# powermon.net
KiCad netlist of a schematic drawn in EAGLE
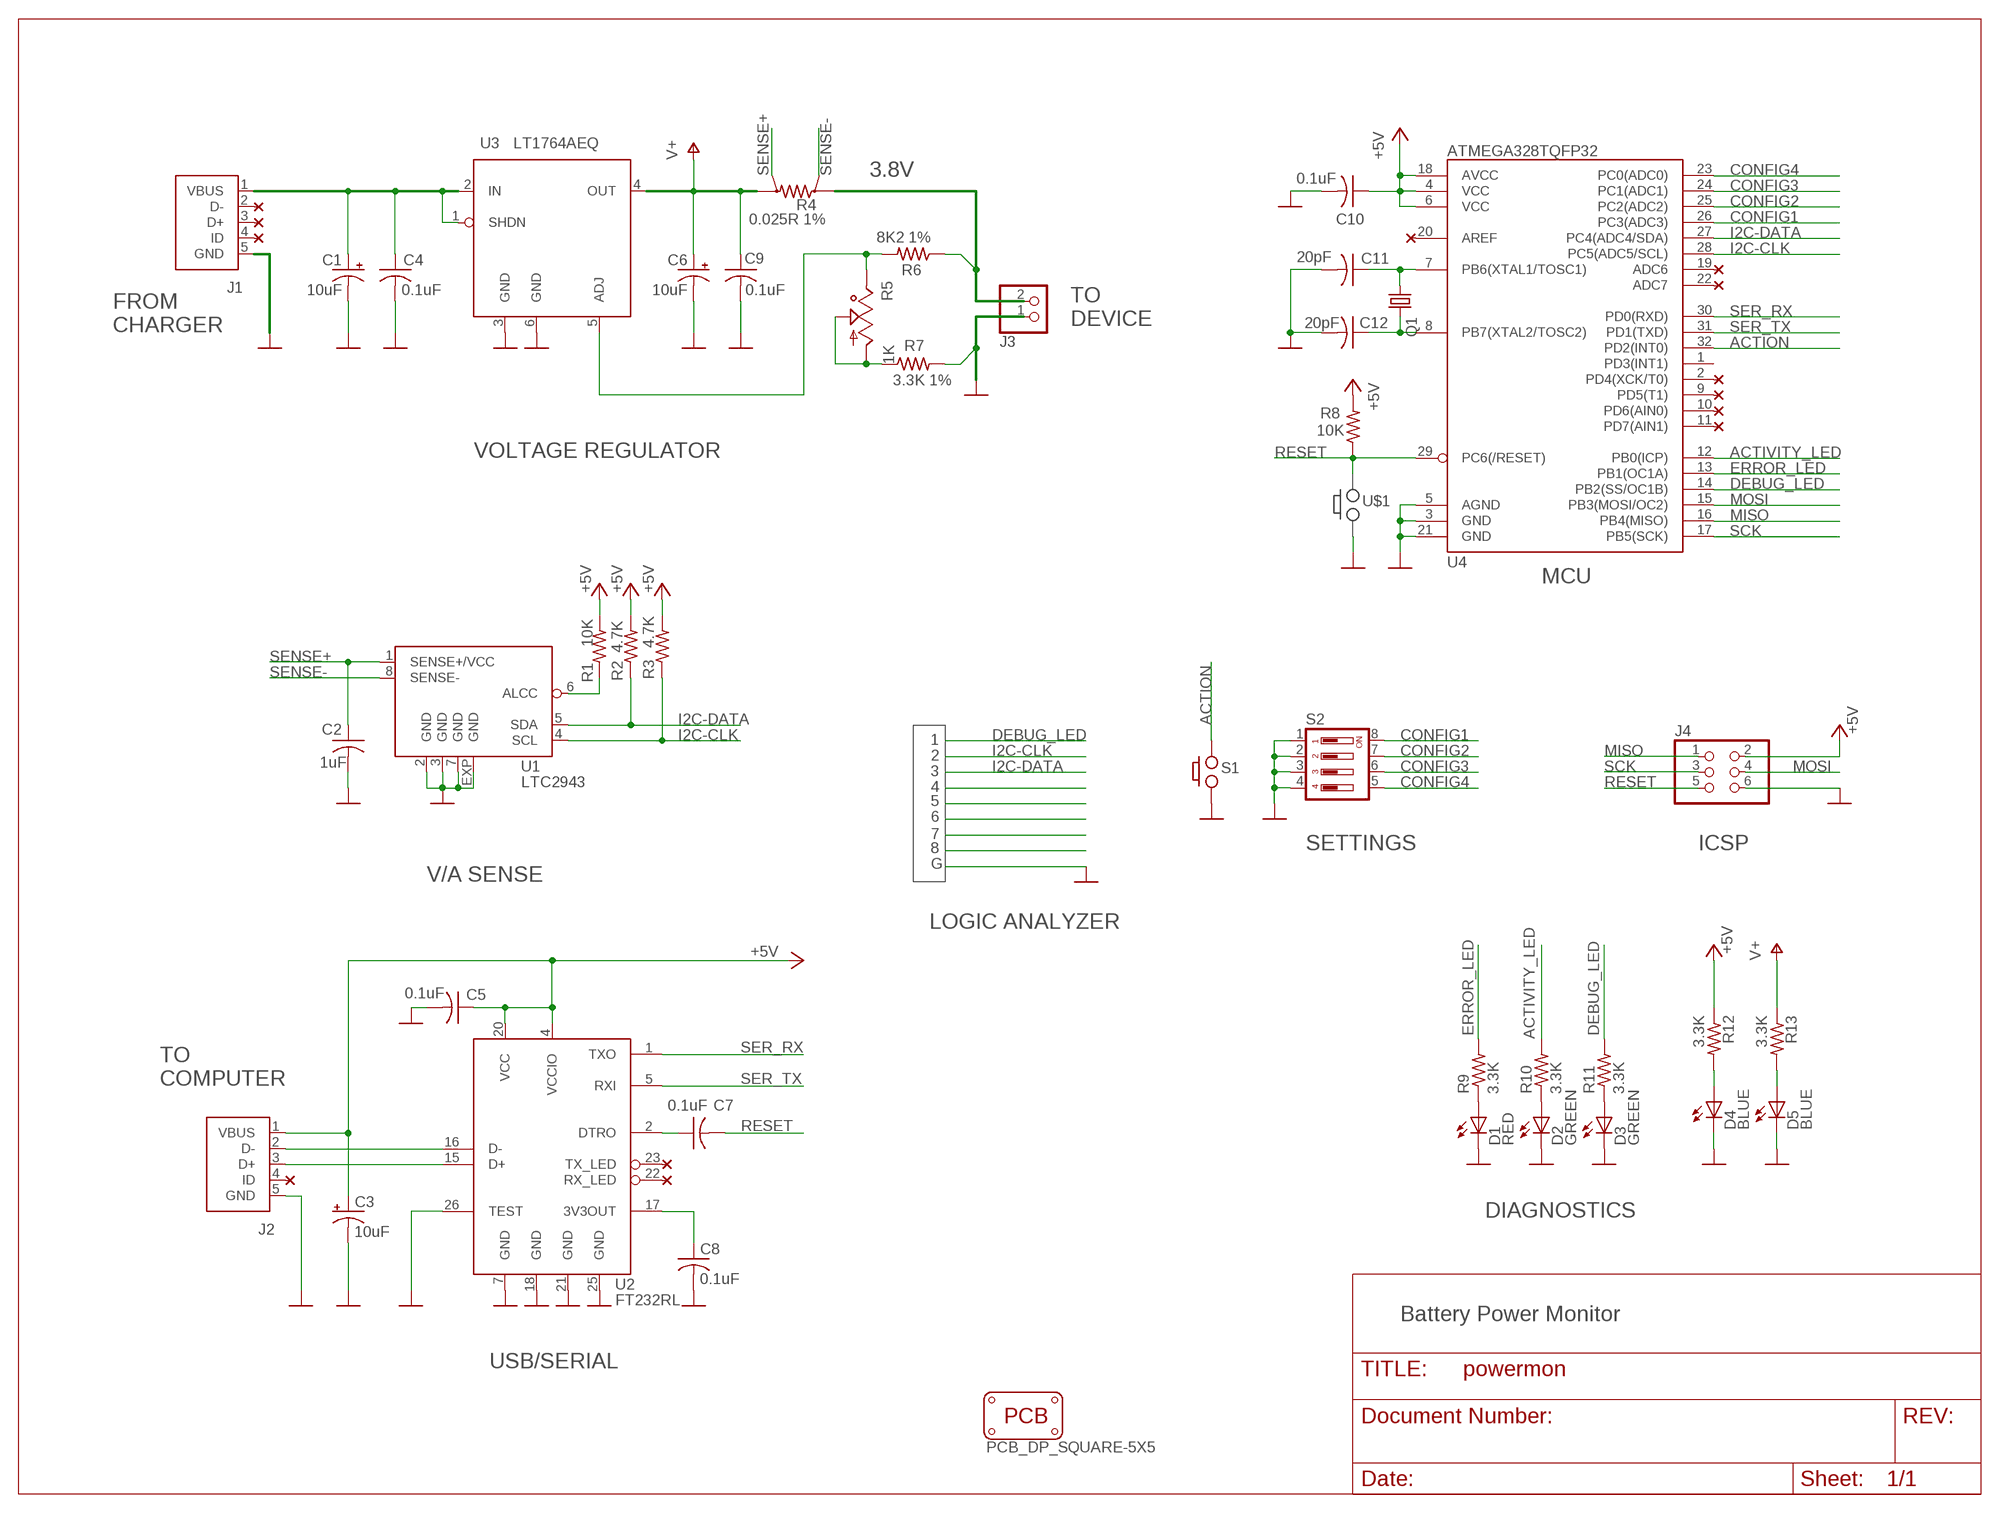
[diagram p0: schematic, sheet 1]

(export (version "E")
  (design (tool "Eeschema 10.0.6"))
  (components
    (comp (ref "C1")
      (value "10uF")
      (footprint "eagle-import:A_3216-18R")
      (libsource (lib "eagle-import") (part "CPOL-USA/3216-18R"))
    )
    (comp (ref "C2")
      (value "1uF")
      (footprint "eagle-import:C0603")
      (libsource (lib "eagle-import") (part "C-USC0603"))
    )
    (comp (ref "C3")
      (value "10uF")
      (footprint "eagle-import:A_3216-18R")
      (libsource (lib "eagle-import") (part "CPOL-USA/3216-18R"))
    )
    (comp (ref "C4")
      (value "0.1uF")
      (footprint "eagle-import:C0603")
      (libsource (lib "eagle-import") (part "C-USC0603"))
    )
    (comp (ref "C5")
      (value "0.1uF")
      (footprint "eagle-import:C0603")
      (libsource (lib "eagle-import") (part "C-USC0603"))
    )
    (comp (ref "C6")
      (value "10uF")
      (footprint "eagle-import:A_3216-18R")
      (libsource (lib "eagle-import") (part "CPOL-USA/3216-18R"))
    )
    (comp (ref "C7")
      (value "0.1uF")
      (footprint "eagle-import:C0603")
      (libsource (lib "eagle-import") (part "C-USC0603"))
    )
    (comp (ref "C8")
      (value "0.1uF")
      (footprint "eagle-import:C0603")
      (libsource (lib "eagle-import") (part "C-USC0603"))
    )
    (comp (ref "C9")
      (value "0.1uF")
      (footprint "eagle-import:C0603")
      (libsource (lib "eagle-import") (part "C-USC0603"))
    )
    (comp (ref "C10")
      (value "0.1uF")
      (footprint "eagle-import:C0603")
      (libsource (lib "eagle-import") (part "C-USC0603"))
    )
    (comp (ref "C11")
      (value "20pF")
      (footprint "eagle-import:C0603")
      (libsource (lib "eagle-import") (part "C-USC0603"))
    )
    (comp (ref "C12")
      (value "20pF")
      (footprint "eagle-import:C0603")
      (libsource (lib "eagle-import") (part "C-USC0603"))
    )
    (comp (ref "D1")
      (value "RED")
      (footprint "eagle-import:1206-LED")
      (libsource (lib "eagle-import") (part "LED"))
    )
    (comp (ref "D2")
      (value "GREEN")
      (footprint "eagle-import:1206-LED")
      (libsource (lib "eagle-import") (part "LED"))
    )
    (comp (ref "D3")
      (value "GREEN")
      (footprint "eagle-import:1206-LED")
      (libsource (lib "eagle-import") (part "LED"))
    )
    (comp (ref "D4")
      (value "BLUE")
      (footprint "eagle-import:1206-LED")
      (libsource (lib "eagle-import") (part "LED"))
    )
    (comp (ref "D5")
      (value "BLUE")
      (footprint "eagle-import:1206-LED")
      (libsource (lib "eagle-import") (part "LED"))
    )
    (comp (ref "J1")
      (value "USB")
      (footprint "eagle-import:USB-MICRO-ZX62RD-AB-5P8")
      (libsource (lib "eagle-import") (part "USB"))
    )
    (comp (ref "J2")
      (value "USB")
      (footprint "eagle-import:USB-MICRO-ZX62RD-AB-5P8")
      (libsource (lib "eagle-import") (part "USB"))
    )
    (comp (ref "J3")
      (value "TERMINAL-2")
      (footprint "eagle-import:TERMINAL-2")
      (libsource (lib "eagle-import") (part "TERMINAL-2"))
    )
    (comp (ref "J4")
      (value "PINHD-2X3")
      (footprint "eagle-import:2X03")
      (libsource (lib "eagle-import") (part "PINHD-2X3"))
    )
    (comp (ref "PCB1")
      (value "PCB_DP_SQUARE-5X5")
      (footprint "eagle-import:DP5050_V1")
      (libsource (lib "eagle-import") (part "PCB_DP_SQUARE-5X5"))
    )
    (comp (ref "Q1")
      (value "CRYSTALCTS406")
      (footprint "eagle-import:CRYSTAL-CTS406")
      (libsource (lib "eagle-import") (part "CRYSTALCTS406"))
    )
    (comp (ref "R1")
      (value "10K")
      (footprint "eagle-import:R0603")
      (libsource (lib "eagle-import") (part "R-US_R0603"))
    )
    (comp (ref "R2")
      (value "4.7K")
      (footprint "eagle-import:R0603")
      (libsource (lib "eagle-import") (part "R-US_R0603"))
    )
    (comp (ref "R3")
      (value "4.7K")
      (footprint "eagle-import:R0603")
      (libsource (lib "eagle-import") (part "R-US_R0603"))
    )
    (comp (ref "R4")
      (value "0.025R 1%")
      (footprint "eagle-import:SHUNT")
      (libsource (lib "eagle-import") (part "SHUNT"))
    )
    (comp (ref "R5")
      (value "1K")
      (footprint "eagle-import:TRIM-POT_SM-42_43A")
      (libsource (lib "eagle-import") (part "TRIM_US-SM-42/43A"))
    )
    (comp (ref "R6")
      (value "8K2 1%")
      (footprint "eagle-import:R0603")
      (libsource (lib "eagle-import") (part "R-US_R0603"))
    )
    (comp (ref "R7")
      (value "3.3K 1%")
      (footprint "eagle-import:R0603")
      (libsource (lib "eagle-import") (part "R-US_R0603"))
    )
    (comp (ref "R8")
      (value "10K")
      (footprint "eagle-import:R0603")
      (libsource (lib "eagle-import") (part "R-US_R0603"))
    )
    (comp (ref "R9")
      (value "3.3K")
      (footprint "eagle-import:R0603")
      (libsource (lib "eagle-import") (part "R-US_R0603"))
    )
    (comp (ref "R10")
      (value "3.3K")
      (footprint "eagle-import:R0603")
      (libsource (lib "eagle-import") (part "R-US_R0603"))
    )
    (comp (ref "R11")
      (value "3.3K")
      (footprint "eagle-import:R0603")
      (libsource (lib "eagle-import") (part "R-US_R0603"))
    )
    (comp (ref "R12")
      (value "3.3K")
      (footprint "eagle-import:R0603")
      (libsource (lib "eagle-import") (part "R-US_R0603"))
    )
    (comp (ref "R13")
      (value "3.3K")
      (footprint "eagle-import:R0603")
      (libsource (lib "eagle-import") (part "R-US_R0603"))
    )
    (comp (ref "S1")
      (value "PUSH_BUTTONEVQPSL")
      (footprint "eagle-import:EVQPSL-PUSH-BUTTON")
      (libsource (lib "eagle-import") (part "PUSH_BUTTONEVQPSL"))
    )
    (comp (ref "S2")
      (value "219-04")
      (footprint "eagle-import:CTS-219-04")
      (libsource (lib "eagle-import") (part "219-04"))
    )
    (comp (ref "U1")
      (value "LTC2943")
      (footprint "eagle-import:DFN8-3X3")
      (libsource (lib "eagle-import") (part "LTC2943"))
    )
    (comp (ref "U2")
      (value "FT232RL")
      (footprint "eagle-import:SSOP28DB")
      (libsource (lib "eagle-import") (part "FT232RL"))
    )
    (comp (ref "U3")
      (value "LT1764AEQ")
      (footprint "eagle-import:TO263-5")
      (libsource (lib "eagle-import") (part "LTE1764"))
    )
    (comp (ref "U4")
      (value "ATMEGA328TQFP32")
      (footprint "eagle-import:TQFP32-08")
      (libsource (lib "eagle-import") (part "ATMEGA328TQFP32"))
    )
  )
  (nets
    (net (code "1") (name "+5V") (class "Default")
      (node (ref "C10") (pin "1") (pinfunction "1_1") (pintype "passive"))
      (node (ref "C3") (pin "+") (pinfunction "+_+") (pintype "passive"))
      (node (ref "C5") (pin "1") (pinfunction "1_1") (pintype "passive"))
      (node (ref "J2") (pin "1") (pinfunction "VBUS_1") (pintype "bidirectional"))
      (node (ref "J4") (pin "2") (pinfunction "2_2") (pintype "passive"))
      (node (ref "R1") (pin "2") (pinfunction "2_2") (pintype "passive"))
      (node (ref "R12") (pin "1") (pinfunction "1_1") (pintype "passive"))
      (node (ref "R2") (pin "2") (pinfunction "2_2") (pintype "passive"))
      (node (ref "R3") (pin "2") (pinfunction "2_2") (pintype "passive"))
      (node (ref "R8") (pin "2") (pinfunction "2_2") (pintype "passive"))
      (node (ref "U2") (pin "20") (pinfunction "VCC_20") (pintype "power_in"))
      (node (ref "U2") (pin "4") (pinfunction "VCCIO_4") (pintype "power_in"))
      (node (ref "U4") (pin "18") (pinfunction "AVCC_18") (pintype "power_in"))
      (node (ref "U4") (pin "4") (pinfunction "VCC_4") (pintype "power_in"))
      (node (ref "U4") (pin "6") (pinfunction "VCC_6") (pintype "power_in"))
    )
    (net (code "2") (name "/ACTION") (class "Default")
      (node (ref "S1") (pin "1") (pinfunction "2_1") (pintype "passive"))
      (node (ref "U4") (pin "32") (pinfunction "PD2(INT0)_32") (pintype "bidirectional"))
    )
    (net (code "3") (name "/ACTIVITY_LED") (class "Default")
      (node (ref "R10") (pin "2") (pinfunction "2_2") (pintype "passive"))
      (node (ref "U4") (pin "12") (pinfunction "PB0(ICP)_12") (pintype "bidirectional"))
    )
    (net (code "4") (name "/AREF") (class "Default")
      (node (ref "U4") (pin "20") (pinfunction "AREF_20") (pintype "power_in"))
    )
    (net (code "5") (name "/CONFIG1") (class "Default")
      (node (ref "S2") (pin "8") (pinfunction "8_8") (pintype "passive"))
      (node (ref "U4") (pin "26") (pinfunction "PC3(ADC3)_26") (pintype "bidirectional"))
    )
    (net (code "6") (name "/CONFIG2") (class "Default")
      (node (ref "S2") (pin "7") (pinfunction "7_7") (pintype "passive"))
      (node (ref "U4") (pin "25") (pinfunction "PC2(ADC2)_25") (pintype "bidirectional"))
    )
    (net (code "7") (name "/CONFIG3") (class "Default")
      (node (ref "S2") (pin "6") (pinfunction "6_6") (pintype "passive"))
      (node (ref "U4") (pin "24") (pinfunction "PC1(ADC1)_24") (pintype "bidirectional"))
    )
    (net (code "8") (name "/CONFIG4") (class "Default")
      (node (ref "S2") (pin "5") (pinfunction "5_5") (pintype "passive"))
      (node (ref "U4") (pin "23") (pinfunction "PC0(ADC0)_23") (pintype "bidirectional"))
    )
    (net (code "9") (name "/DEBUG_LED") (class "Default")
      (node (ref "R11") (pin "2") (pinfunction "2_2") (pintype "passive"))
      (node (ref "U4") (pin "14") (pinfunction "PB2(SS/OC1B)_14") (pintype "bidirectional"))
    )
    (net (code "10") (name "/ERROR_LED") (class "Default")
      (node (ref "R9") (pin "2") (pinfunction "2_2") (pintype "passive"))
      (node (ref "U4") (pin "13") (pinfunction "PB1(OC1A)_13") (pintype "bidirectional"))
    )
    (net (code "11") (name "/I2C-CLK") (class "Default")
      (node (ref "R3") (pin "1") (pinfunction "1_1") (pintype "passive"))
      (node (ref "U1") (pin "4") (pinfunction "SCL_4") (pintype "input"))
      (node (ref "U4") (pin "28") (pinfunction "PC5(ADC5/SCL)_28") (pintype "bidirectional"))
    )
    (net (code "12") (name "/I2C-DATA") (class "Default")
      (node (ref "R2") (pin "1") (pinfunction "1_1") (pintype "passive"))
      (node (ref "U1") (pin "5") (pinfunction "SDA_5") (pintype "bidirectional"))
      (node (ref "U4") (pin "27") (pinfunction "PC4(ADC4/SDA)_27") (pintype "bidirectional"))
    )
    (net (code "13") (name "/MISO") (class "Default")
      (node (ref "J4") (pin "1") (pinfunction "1_1") (pintype "passive"))
      (node (ref "U4") (pin "16") (pinfunction "PB4(MISO)_16") (pintype "bidirectional"))
    )
    (net (code "14") (name "/MOSI") (class "Default")
      (node (ref "J4") (pin "4") (pinfunction "4_4") (pintype "passive"))
      (node (ref "U4") (pin "15") (pinfunction "PB3(MOSI/OC2)_15") (pintype "bidirectional"))
    )
    (net (code "15") (name "/RESET") (class "Default")
      (node (ref "C7") (pin "2") (pinfunction "2_2") (pintype "passive"))
      (node (ref "J4") (pin "5") (pinfunction "5_5") (pintype "passive"))
      (node (ref "R8") (pin "1") (pinfunction "1_1") (pintype "passive"))
      (node (ref "U4") (pin "29") (pinfunction "PC6(/RESET)_29") (pintype "bidirectional"))
    )
    (net (code "16") (name "/SCK") (class "Default")
      (node (ref "J4") (pin "3") (pinfunction "3_3") (pintype "passive"))
      (node (ref "U4") (pin "17") (pinfunction "PB5(SCK)_17") (pintype "bidirectional"))
    )
    (net (code "17") (name "/SENSE+") (class "Default")
      (node (ref "C2") (pin "1") (pinfunction "1_1") (pintype "passive"))
      (node (ref "R4") (pin "V2") (pinfunction "V2_V2") (pintype "passive"))
      (node (ref "U1") (pin "1") (pinfunction "SENSE+/VCC_1") (pintype "passive"))
    )
    (net (code "18") (name "/SENSE-") (class "Default")
      (node (ref "R4") (pin "V1") (pinfunction "V1_V1") (pintype "passive"))
      (node (ref "U1") (pin "8") (pinfunction "SENSE-_8") (pintype "passive"))
    )
    (net (code "19") (name "/SER_RX") (class "Default")
      (node (ref "U2") (pin "1") (pinfunction "TXO_1") (pintype "output"))
      (node (ref "U4") (pin "30") (pinfunction "PD0(RXD)_30") (pintype "bidirectional"))
    )
    (net (code "20") (name "/SER_TX") (class "Default")
      (node (ref "U2") (pin "5") (pinfunction "RXI_5") (pintype "input"))
      (node (ref "U4") (pin "31") (pinfunction "PD1(TXD)_31") (pintype "bidirectional"))
    )
    (net (code "21") (name "GND") (class "Default")
      (node (ref "C1") (pin "-") (pinfunction "-_-") (pintype "passive"))
      (node (ref "C10") (pin "2") (pinfunction "2_2") (pintype "passive"))
      (node (ref "C11") (pin "2") (pinfunction "2_2") (pintype "passive"))
      (node (ref "C12") (pin "2") (pinfunction "2_2") (pintype "passive"))
      (node (ref "C2") (pin "2") (pinfunction "2_2") (pintype "passive"))
      (node (ref "C3") (pin "-") (pinfunction "-_-") (pintype "passive"))
      (node (ref "C4") (pin "2") (pinfunction "2_2") (pintype "passive"))
      (node (ref "C5") (pin "2") (pinfunction "2_2") (pintype "passive"))
      (node (ref "C6") (pin "-") (pinfunction "-_-") (pintype "passive"))
      (node (ref "C8") (pin "2") (pinfunction "2_2") (pintype "passive"))
      (node (ref "C9") (pin "2") (pinfunction "2_2") (pintype "passive"))
      (node (ref "D1") (pin "C") (pinfunction "C_C") (pintype "passive"))
      (node (ref "D2") (pin "C") (pinfunction "C_C") (pintype "passive"))
      (node (ref "D3") (pin "C") (pinfunction "C_C") (pintype "passive"))
      (node (ref "D4") (pin "C") (pinfunction "C_C") (pintype "passive"))
      (node (ref "D5") (pin "C") (pinfunction "C_C") (pintype "passive"))
      (node (ref "J1") (pin "5") (pinfunction "GND_5") (pintype "bidirectional"))
      (node (ref "J2") (pin "5") (pinfunction "GND_5") (pintype "bidirectional"))
      (node (ref "J3") (pin "1") (pinfunction "1_1") (pintype "passive"))
      (node (ref "J4") (pin "6") (pinfunction "6_6") (pintype "passive"))
      (node (ref "R7") (pin "2") (pinfunction "2_2") (pintype "passive"))
      (node (ref "S1") (pin "2") (pinfunction "1_2") (pintype "passive"))
      (node (ref "S2") (pin "1") (pinfunction "1_1") (pintype "passive"))
      (node (ref "S2") (pin "2") (pinfunction "2_2") (pintype "passive"))
      (node (ref "S2") (pin "3") (pinfunction "3_3") (pintype "passive"))
      (node (ref "S2") (pin "4") (pinfunction "4_4") (pintype "passive"))
      (node (ref "U1") (pin "2") (pinfunction "GND_2") (pintype "power_in"))
      (node (ref "U1") (pin "3") (pinfunction "GND_3") (pintype "power_in"))
      (node (ref "U1") (pin "7") (pinfunction "GND_7") (pintype "power_in"))
      (node (ref "U1") (pin "EXP") (pinfunction "GND_EXP") (pintype "power_in"))
      (node (ref "U2") (pin "18") (pinfunction "GND_18") (pintype "power_in"))
      (node (ref "U2") (pin "21") (pinfunction "GND_21") (pintype "power_in"))
      (node (ref "U2") (pin "25") (pinfunction "GND_25") (pintype "power_in"))
      (node (ref "U2") (pin "26") (pinfunction "TEST_26") (pintype "input"))
      (node (ref "U2") (pin "7") (pinfunction "GND_7") (pintype "power_in"))
      (node (ref "U3") (pin "3") (pinfunction "GND_3") (pintype "bidirectional"))
      (node (ref "U3") (pin "6") (pinfunction "GND_6") (pintype "bidirectional"))
      (node (ref "U4") (pin "21") (pinfunction "GND_21") (pintype "power_in"))
      (node (ref "U4") (pin "3") (pinfunction "GND_3") (pintype "power_in"))
      (node (ref "U4") (pin "5") (pinfunction "AGND_5") (pintype "power_in"))
    )
    (net (code "22") (name "Net-(D1-PadA)") (class "Default")
      (node (ref "D1") (pin "A") (pinfunction "A_A") (pintype "passive"))
      (node (ref "R9") (pin "1") (pinfunction "1_1") (pintype "passive"))
    )
    (net (code "23") (name "Net-(D2-PadA)") (class "Default")
      (node (ref "D2") (pin "A") (pinfunction "A_A") (pintype "passive"))
      (node (ref "R10") (pin "1") (pinfunction "1_1") (pintype "passive"))
    )
    (net (code "24") (name "Net-(D3-PadA)") (class "Default")
      (node (ref "D3") (pin "A") (pinfunction "A_A") (pintype "passive"))
      (node (ref "R11") (pin "1") (pinfunction "1_1") (pintype "passive"))
    )
    (net (code "25") (name "Net-(D4-PadA)") (class "Default")
      (node (ref "D4") (pin "A") (pinfunction "A_A") (pintype "passive"))
      (node (ref "R12") (pin "2") (pinfunction "2_2") (pintype "passive"))
    )
    (net (code "26") (name "Net-(D5-PadA)") (class "Default")
      (node (ref "D5") (pin "A") (pinfunction "A_A") (pintype "passive"))
      (node (ref "R13") (pin "2") (pinfunction "2_2") (pintype "passive"))
    )
    (net (code "27") (name "Net-(J1-VBUS)") (class "Default")
      (node (ref "C1") (pin "+") (pinfunction "+_+") (pintype "passive"))
      (node (ref "C4") (pin "1") (pinfunction "1_1") (pintype "passive"))
      (node (ref "J1") (pin "1") (pinfunction "VBUS_1") (pintype "bidirectional"))
      (node (ref "U3") (pin "1") (pinfunction "SHDN_1") (pintype "bidirectional"))
      (node (ref "U3") (pin "2") (pinfunction "IN_2") (pintype "bidirectional"))
    )
    (net (code "28") (name "Net-(J2-D+)") (class "Default")
      (node (ref "J2") (pin "3") (pinfunction "D+_3") (pintype "bidirectional"))
      (node (ref "U2") (pin "15") (pinfunction "D+_15") (pintype "passive"))
    )
    (net (code "29") (name "Net-(J2-D-)") (class "Default")
      (node (ref "J2") (pin "2") (pinfunction "D-_2") (pintype "bidirectional"))
      (node (ref "U2") (pin "16") (pinfunction "D-_16") (pintype "passive"))
    )
    (net (code "30") (name "Net-(J3-Pad2)") (class "Default")
      (node (ref "J3") (pin "2") (pinfunction "2_2") (pintype "passive"))
      (node (ref "R4") (pin "I1") (pinfunction "I1_I1") (pintype "passive"))
      (node (ref "R6") (pin "1") (pinfunction "1_1") (pintype "passive"))
    )
    (net (code "31") (name "Net-(Q1-2)") (class "Default")
      (node (ref "C12") (pin "1") (pinfunction "1_1") (pintype "passive"))
      (node (ref "Q1") (pin "3") (pinfunction "2_3") (pintype "passive"))
      (node (ref "U4") (pin "8") (pinfunction "PB7(XTAL2/TOSC2)_8") (pintype "bidirectional"))
    )
    (net (code "32") (name "Net-(R5-Pad1)") (class "Default")
      (node (ref "R5") (pin "1") (pinfunction "1_1") (pintype "passive"))
      (node (ref "R5") (pin "2") (pinfunction "2_2") (pintype "passive"))
      (node (ref "R7") (pin "1") (pinfunction "1_1") (pintype "passive"))
    )
    (net (code "33") (name "Net-(U1-ALCC)") (class "Default")
      (node (ref "R1") (pin "1") (pinfunction "1_1") (pintype "passive"))
      (node (ref "U1") (pin "6") (pinfunction "ALCC_6") (pintype "open_collector"))
    )
    (net (code "34") (name "Net-(U2-3V3OUT)") (class "Default")
      (node (ref "C8") (pin "1") (pinfunction "1_1") (pintype "passive"))
      (node (ref "U2") (pin "17") (pinfunction "3V3OUT_17") (pintype "power_in"))
    )
    (net (code "35") (name "Net-(U2-DTRO)") (class "Default")
      (node (ref "C7") (pin "1") (pinfunction "1_1") (pintype "passive"))
      (node (ref "U2") (pin "2") (pinfunction "DTRO_2") (pintype "output"))
    )
    (net (code "36") (name "Net-(U3-ADJ)") (class "Default")
      (node (ref "R5") (pin "3") (pinfunction "3_3") (pintype "passive"))
      (node (ref "R6") (pin "2") (pinfunction "2_2") (pintype "passive"))
      (node (ref "U3") (pin "5") (pinfunction "ADJ_5") (pintype "bidirectional"))
    )
    (net (code "37") (name "Net-(U4-PB6(XTAL1{slash}TOSC1))") (class "Default")
      (node (ref "C11") (pin "1") (pinfunction "1_1") (pintype "passive"))
      (node (ref "Q1") (pin "1") (pinfunction "1_1") (pintype "passive"))
      (node (ref "U4") (pin "7") (pinfunction "PB6(XTAL1/TOSC1)_7") (pintype "bidirectional"))
    )
    (net (code "38") (name "V+") (class "Default")
      (node (ref "C6") (pin "+") (pinfunction "+_+") (pintype "passive"))
      (node (ref "C9") (pin "1") (pinfunction "1_1") (pintype "passive"))
      (node (ref "R13") (pin "1") (pinfunction "1_1") (pintype "passive"))
      (node (ref "R4") (pin "I2") (pinfunction "I2_I2") (pintype "passive"))
      (node (ref "U3") (pin "4") (pinfunction "OUT_4") (pintype "bidirectional"))
    )
    (net (code "39") (name "unconnected-(J1-D+-Pad3)") (class "Default")
      (node (ref "J1") (pin "3") (pinfunction "D+_3") (pintype "bidirectional"))
    )
    (net (code "40") (name "unconnected-(J1-D--Pad2)") (class "Default")
      (node (ref "J1") (pin "2") (pinfunction "D-_2") (pintype "bidirectional"))
    )
    (net (code "41") (name "unconnected-(J1-ID-Pad4)") (class "Default")
      (node (ref "J1") (pin "4") (pinfunction "ID_4") (pintype "bidirectional"))
    )
    (net (code "42") (name "unconnected-(J2-ID-Pad4)") (class "Default")
      (node (ref "J2") (pin "4") (pinfunction "ID_4") (pintype "bidirectional"))
    )
    (net (code "43") (name "unconnected-(U2-RX_LED-Pad22)") (class "Default")
      (node (ref "U2") (pin "22") (pinfunction "RX_LED_22") (pintype "output"))
    )
    (net (code "44") (name "unconnected-(U2-TX_LED-Pad23)") (class "Default")
      (node (ref "U2") (pin "23") (pinfunction "TX_LED_23") (pintype "output"))
    )
    (net (code "45") (name "unconnected-(U4-ADC6-Pad19)") (class "Default")
      (node (ref "U4") (pin "19") (pinfunction "ADC6_19") (pintype "bidirectional"))
    )
    (net (code "46") (name "unconnected-(U4-ADC7-Pad22)") (class "Default")
      (node (ref "U4") (pin "22") (pinfunction "ADC7_22") (pintype "bidirectional"))
    )
    (net (code "47") (name "unconnected-(U4-PD3(INT1)-Pad1)") (class "Default")
      (node (ref "U4") (pin "1") (pinfunction "PD3(INT1)_1") (pintype "bidirectional"))
    )
    (net (code "48") (name "unconnected-(U4-PD4(XCK{slash}T0)-Pad2)") (class "Default")
      (node (ref "U4") (pin "2") (pinfunction "PD4(XCK/T0)_2") (pintype "bidirectional"))
    )
    (net (code "49") (name "unconnected-(U4-PD5(T1)-Pad9)") (class "Default")
      (node (ref "U4") (pin "9") (pinfunction "PD5(T1)_9") (pintype "bidirectional"))
    )
    (net (code "50") (name "unconnected-(U4-PD6(AIN0)-Pad10)") (class "Default")
      (node (ref "U4") (pin "10") (pinfunction "PD6(AIN0)_10") (pintype "bidirectional"))
    )
    (net (code "51") (name "unconnected-(U4-PD7(AIN1)-Pad11)") (class "Default")
      (node (ref "U4") (pin "11") (pinfunction "PD7(AIN1)_11") (pintype "bidirectional"))
    )
  )
)
